# SecondSheet.net
KiCad netlist of a schematic drawn in Altium Designer
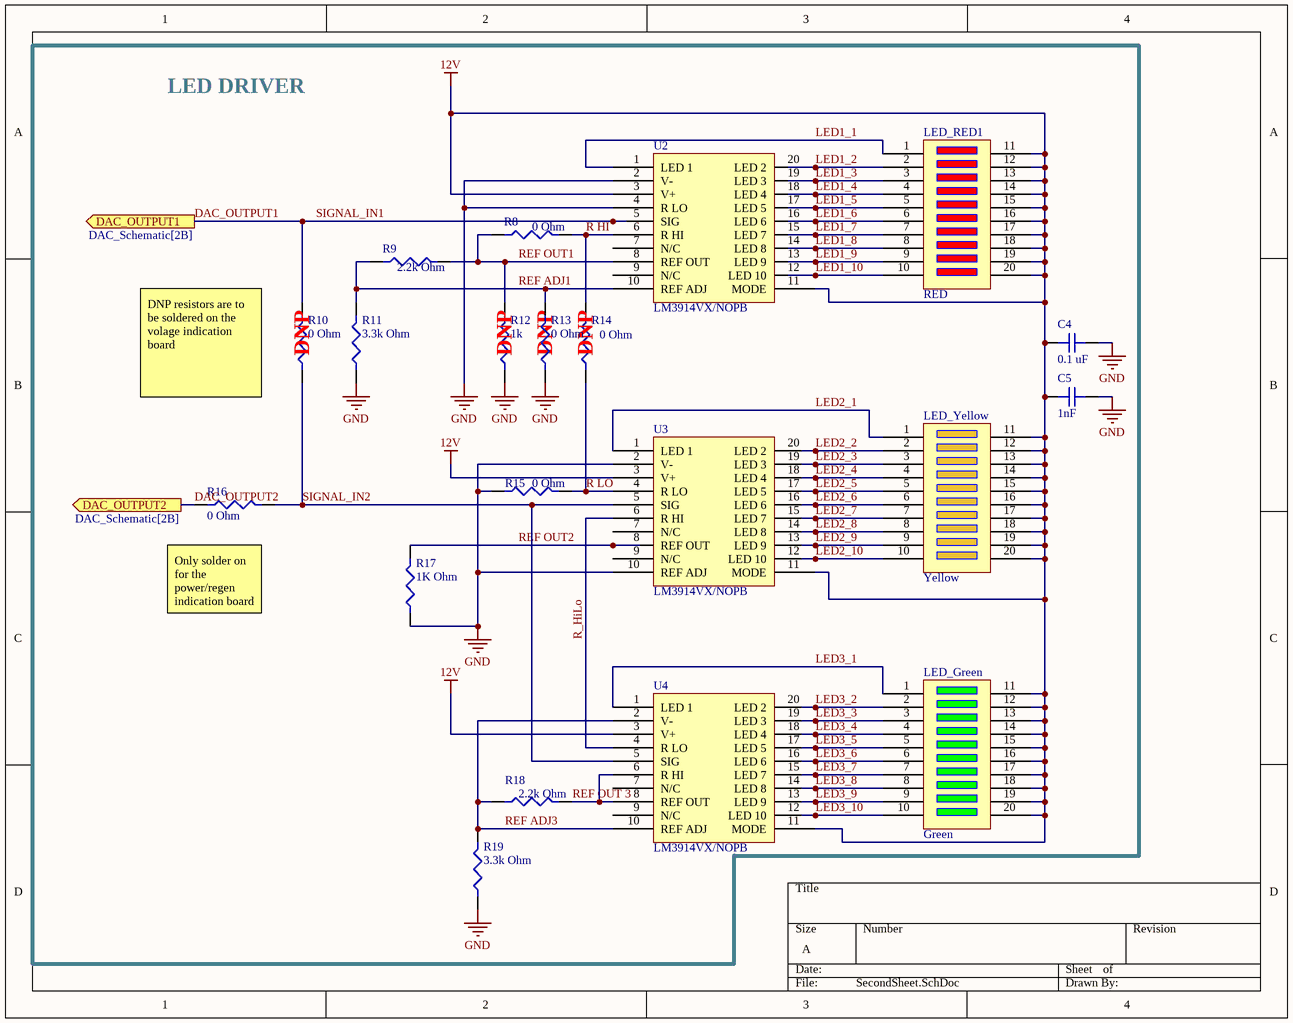
[diagram p0: SecondSheet.SchDoc]

(export (version "E")
  (design (tool "Eeschema 10.0.6"))
  (components
    (comp (ref "C4")
      (value "0.1 uF")
      (footprint "CAPC1608X09N")
      (fields
        (field (name "MANUFACTURER") "KEMET")
        (field (name "MANUFACTURER PART NUMBER") "C0603C104Z3VACTU")
        (field (name "TOLERANCE") "80%")
      )
      (libsource (lib "Dash_Schematic") (part "C0603C104Z3VACTU"))
    )
    (comp (ref "C5")
      (value "1nF")
      (footprint "CAPC1608X09N")
      (description "CAP CER 1000PF 50V X7R 0603")
      (fields
        (field (name "MANUFACTURER") "Yageo")
        (field (name "MANUFACTURER PART NUMBER") "CC0603KRX7R9BB102")
      )
      (libsource (lib "Dash_Schematic") (part "CC0603KRX7R9BB102"))
    )
    (comp (ref "LED_Green")
      (value "Green")
      (footprint "DIP20")
      (description "LED BAR GRAPH 10-SEGMENT GREEN")
      (fields
        (field (name "MANUFACTURER") "Vishay Lite-On")
        (field (name "MANUFACTURER PART NUMBER") "LTA-1000G")
      )
      (libsource (lib "Dash_Schematic") (part "LTA-1000G"))
    )
    (comp (ref "LED_RED1")
      (value "RED")
      (footprint "DIP20")
      (description "LED BAR GRAPH 10-SEGMENT RED")
      (fields
        (field (name "MANUFACTURER") "Vishay Lite-On")
        (field (name "MANUFACTURER PART NUMBER") "LTA-1000HR")
      )
      (libsource (lib "Dash_Schematic") (part "LTA-1000HR"))
    )
    (comp (ref "LED_Yellow")
      (value "Yellow")
      (footprint "DIP20")
      (description "LED BAR GRAPH 10-SEGMENT YELLOW")
      (fields
        (field (name "MANUFACTURER") "Vishay Lite-On")
        (field (name "MANUFACTURER PART NUMBER") "LTA-1000Y")
      )
      (libsource (lib "Dash_Schematic") (part "LTA-1000Y"))
    )
    (comp (ref "R8")
      (value "0 Ohm")
      (footprint "RESC2012X06N")
      (description "RES 0 OHM JUMPER 1/8W 0805")
      (fields
        (field (name "MANUFACTURER") "Stackpole Electronics")
        (field (name "MANUFACTURER PART NUMBER") "RMCF0805ZT0R00")
      )
      (libsource (lib "Dash_Schematic") (part "RMCF0805ZT0R00"))
    )
    (comp (ref "R9")
      (value "2.2k Ohm")
      (footprint "RESC2012X06N")
      (description "RES SMD 2.2K OHM 1% 1/8W 0805")
      (fields
        (field (name "MANUFACTURER") "Yageo")
        (field (name "MANUFACTURER PART NUMBER") "RC0805FR-072K2L")
      )
      (libsource (lib "Dash_Schematic") (part "RC0805FR-072K2L"))
    )
    (comp (ref "R10")
      (value "0 Ohm")
      (footprint "RESC2012X06N")
      (description "RES 0 OHM JUMPER 1/8W 0805")
      (fields
        (field (name "MANUFACTURER") "Stackpole Electronics")
        (field (name "MANUFACTURER PART NUMBER") "RMCF0805ZT0R00")
      )
      (libsource (lib "Dash_Schematic") (part "RMCF0805ZT0R00"))
    )
    (comp (ref "R11")
      (value "3.3k Ohm")
      (footprint "RESC2012X06N")
      (description "Thin Film Resistors - SMD 0805 1/8W 3.3Kohms")
      (fields
        (field (name "MANUFACTURER") "Panasonic")
        (field (name "MANUFACTURER PART NUMBER") "ERA-6AEB332V")
      )
      (libsource (lib "Dash_Schematic") (part "ERA-6AEB332V"))
    )
    (comp (ref "R12")
      (value "1k")
      (footprint "RESC2012X06N")
      (description "RES 0 OHM JUMPER 1/8W 0805")
      (fields
        (field (name "MANUFACTURER") "Stackpole Electronics")
        (field (name "MANUFACTURER PART NUMBER") "RMCF0805ZT0R00")
      )
      (libsource (lib "Dash_Schematic") (part "RMCF0805ZT0R00"))
    )
    (comp (ref "R13")
      (value "0 Ohm")
      (footprint "RESC2012X06N")
      (description "RES 0 OHM JUMPER 1/8W 0805")
      (fields
        (field (name "MANUFACTURER") "Stackpole Electronics")
        (field (name "MANUFACTURER PART NUMBER") "RMCF0805ZT0R00")
      )
      (libsource (lib "Dash_Schematic") (part "RMCF0805ZT0R00"))
    )
    (comp (ref "R14")
      (value "0 Ohm")
      (footprint "RESC2012X06N")
      (description "RES 0 OHM JUMPER 1/8W 0805")
      (fields
        (field (name "MANUFACTURER") "Stackpole Electronics")
        (field (name "MANUFACTURER PART NUMBER") "RMCF0805ZT0R00")
      )
      (libsource (lib "Dash_Schematic") (part "RMCF0805ZT0R00"))
    )
    (comp (ref "R15")
      (value "0 Ohm")
      (footprint "RESC2012X06N")
      (description "RES 0 OHM JUMPER 1/8W 0805")
      (fields
        (field (name "MANUFACTURER") "Stackpole Electronics")
        (field (name "MANUFACTURER PART NUMBER") "RMCF0805ZT0R00")
      )
      (libsource (lib "Dash_Schematic") (part "RMCF0805ZT0R00"))
    )
    (comp (ref "R16")
      (value "0 Ohm")
      (footprint "RESC2012X06N")
      (description "RES 0 OHM JUMPER 1/8W 0805")
      (fields
        (field (name "MANUFACTURER") "Stackpole Electronics")
        (field (name "MANUFACTURER PART NUMBER") "RMCF0805ZT0R00")
      )
      (libsource (lib "Dash_Schematic") (part "RMCF0805ZT0R00"))
    )
    (comp (ref "R17")
      (value "1K Ohm")
      (footprint "RESC2012X06N")
      (description "RES SMD 1K OHM 5% 1/8W 0805")
      (fields
        (field (name "MANUFACTURER") "Yageo")
        (field (name "MANUFACTURER PART NUMBER") "RC0805JR-071KL")
      )
      (libsource (lib "Dash_Schematic") (part "RC0805JR-071KL"))
    )
    (comp (ref "R18")
      (value "2.2k Ohm")
      (footprint "RESC2012X06N")
      (description "RES SMD 2.2K OHM 1% 1/8W 0805")
      (fields
        (field (name "MANUFACTURER") "Yageo")
        (field (name "MANUFACTURER PART NUMBER") "RC0805FR-072K2L")
      )
      (libsource (lib "Dash_Schematic") (part "RC0805FR-072K2L"))
    )
    (comp (ref "R19")
      (value "3.3k Ohm")
      (footprint "RESC2012X06N")
      (description "Thin Film Resistors - SMD 0805 1/8W 3.3Kohms")
      (fields
        (field (name "MANUFACTURER") "Panasonic")
        (field (name "MANUFACTURER PART NUMBER") "ERA-6AEB332V")
      )
      (libsource (lib "Dash_Schematic") (part "ERA-6AEB332V"))
    )
    (comp (ref "U2")
      (value "LM3914VX/NOPB")
      (footprint "PLCC127P990X990X457-20N")
      (description "LED DRVR 10Segment 20-Pin PLCC T/R")
      (fields (field (name "MANUFACTURER") "TI National Semiconductor"))
      (libsource (lib "Dash_Schematic") (part "LM3914VX/NOPB"))
    )
    (comp (ref "U3")
      (value "LM3914VX/NOPB")
      (footprint "PLCC127P990X990X457-20N")
      (description "LED DRVR 10Segment 20-Pin PLCC T/R")
      (fields (field (name "MANUFACTURER") "TI National Semiconductor"))
      (libsource (lib "Dash_Schematic") (part "LM3914VX/NOPB"))
    )
    (comp (ref "U4")
      (value "LM3914VX/NOPB")
      (footprint "PLCC127P990X990X457-20N")
      (description "LED DRVR 10Segment 20-Pin PLCC T/R")
      (fields (field (name "MANUFACTURER") "TI National Semiconductor"))
      (libsource (lib "Dash_Schematic") (part "LM3914VX/NOPB"))
    )
  )
  (nets
    (net (code "1") (name "/DAC_OUTPUT1") (class "Default")
      (node (ref "R10") (pin "2") (pinfunction "2_2") (pintype "passive"))
      (node (ref "U2") (pin "5") (pinfunction "SIG_5") (pintype "passive"))
    )
    (net (code "2") (name "/DAC_OUTPUT2") (class "Default")
      (node (ref "R16") (pin "1") (pinfunction "1_1") (pintype "passive"))
    )
    (net (code "3") (name "/LED1_1") (class "Default")
      (node (ref "LED_RED1") (pin "1") (pinfunction "1_1") (pintype "passive"))
      (node (ref "U2") (pin "1") (pinfunction "LED_1_1") (pintype "passive"))
    )
    (net (code "4") (name "/LED1_2") (class "Default")
      (node (ref "LED_RED1") (pin "2") (pinfunction "2_2") (pintype "passive"))
      (node (ref "U2") (pin "20") (pinfunction "LED_2_20") (pintype "passive"))
    )
    (net (code "5") (name "/LED1_3") (class "Default")
      (node (ref "LED_RED1") (pin "3") (pinfunction "3_3") (pintype "passive"))
      (node (ref "U2") (pin "19") (pinfunction "LED_3_19") (pintype "passive"))
    )
    (net (code "6") (name "/LED1_4") (class "Default")
      (node (ref "LED_RED1") (pin "4") (pinfunction "4_4") (pintype "passive"))
      (node (ref "U2") (pin "18") (pinfunction "LED_4_18") (pintype "passive"))
    )
    (net (code "7") (name "/LED1_5") (class "Default")
      (node (ref "LED_RED1") (pin "5") (pinfunction "5_5") (pintype "passive"))
      (node (ref "U2") (pin "17") (pinfunction "LED_5_17") (pintype "passive"))
    )
    (net (code "8") (name "/LED1_6") (class "Default")
      (node (ref "LED_RED1") (pin "6") (pinfunction "6_6") (pintype "passive"))
      (node (ref "U2") (pin "16") (pinfunction "LED_6_16") (pintype "passive"))
    )
    (net (code "9") (name "/LED1_7") (class "Default")
      (node (ref "LED_RED1") (pin "7") (pinfunction "7_7") (pintype "passive"))
      (node (ref "U2") (pin "15") (pinfunction "LED_7_15") (pintype "passive"))
    )
    (net (code "10") (name "/LED1_8") (class "Default")
      (node (ref "LED_RED1") (pin "8") (pinfunction "8_8") (pintype "passive"))
      (node (ref "U2") (pin "14") (pinfunction "LED_8_14") (pintype "passive"))
    )
    (net (code "11") (name "/LED1_9") (class "Default")
      (node (ref "LED_RED1") (pin "9") (pinfunction "9_9") (pintype "passive"))
      (node (ref "U2") (pin "13") (pinfunction "LED_9_13") (pintype "passive"))
    )
    (net (code "12") (name "/LED1_10") (class "Default")
      (node (ref "LED_RED1") (pin "10") (pinfunction "10_10") (pintype "passive"))
      (node (ref "U2") (pin "12") (pinfunction "LED_10_12") (pintype "passive"))
    )
    (net (code "13") (name "/LED2_1") (class "Default")
      (node (ref "LED_Yellow") (pin "1") (pinfunction "1_1") (pintype "passive"))
      (node (ref "U3") (pin "1") (pinfunction "LED_1_1") (pintype "passive"))
    )
    (net (code "14") (name "/LED2_2") (class "Default")
      (node (ref "LED_Yellow") (pin "2") (pinfunction "2_2") (pintype "passive"))
      (node (ref "U3") (pin "20") (pinfunction "LED_2_20") (pintype "passive"))
    )
    (net (code "15") (name "/LED2_3") (class "Default")
      (node (ref "LED_Yellow") (pin "3") (pinfunction "3_3") (pintype "passive"))
      (node (ref "U3") (pin "19") (pinfunction "LED_3_19") (pintype "passive"))
    )
    (net (code "16") (name "/LED2_4") (class "Default")
      (node (ref "LED_Yellow") (pin "4") (pinfunction "4_4") (pintype "passive"))
      (node (ref "U3") (pin "18") (pinfunction "LED_4_18") (pintype "passive"))
    )
    (net (code "17") (name "/LED2_5") (class "Default")
      (node (ref "LED_Yellow") (pin "5") (pinfunction "5_5") (pintype "passive"))
      (node (ref "U3") (pin "17") (pinfunction "LED_5_17") (pintype "passive"))
    )
    (net (code "18") (name "/LED2_6") (class "Default")
      (node (ref "LED_Yellow") (pin "6") (pinfunction "6_6") (pintype "passive"))
      (node (ref "U3") (pin "16") (pinfunction "LED_6_16") (pintype "passive"))
    )
    (net (code "19") (name "/LED2_7") (class "Default")
      (node (ref "LED_Yellow") (pin "7") (pinfunction "7_7") (pintype "passive"))
      (node (ref "U3") (pin "15") (pinfunction "LED_7_15") (pintype "passive"))
    )
    (net (code "20") (name "/LED2_8") (class "Default")
      (node (ref "LED_Yellow") (pin "8") (pinfunction "8_8") (pintype "passive"))
      (node (ref "U3") (pin "14") (pinfunction "LED_8_14") (pintype "passive"))
    )
    (net (code "21") (name "/LED2_9") (class "Default")
      (node (ref "LED_Yellow") (pin "9") (pinfunction "9_9") (pintype "passive"))
      (node (ref "U3") (pin "13") (pinfunction "LED_9_13") (pintype "passive"))
    )
    (net (code "22") (name "/LED2_10") (class "Default")
      (node (ref "LED_Yellow") (pin "10") (pinfunction "10_10") (pintype "passive"))
      (node (ref "U3") (pin "12") (pinfunction "LED_10_12") (pintype "passive"))
    )
    (net (code "23") (name "/LED3_1") (class "Default")
      (node (ref "LED_Green") (pin "1") (pinfunction "1_1") (pintype "passive"))
      (node (ref "U4") (pin "1") (pinfunction "LED_1_1") (pintype "passive"))
    )
    (net (code "24") (name "/LED3_2") (class "Default")
      (node (ref "LED_Green") (pin "2") (pinfunction "2_2") (pintype "passive"))
      (node (ref "U4") (pin "20") (pinfunction "LED_2_20") (pintype "passive"))
    )
    (net (code "25") (name "/LED3_3") (class "Default")
      (node (ref "LED_Green") (pin "3") (pinfunction "3_3") (pintype "passive"))
      (node (ref "U4") (pin "19") (pinfunction "LED_3_19") (pintype "passive"))
    )
    (net (code "26") (name "/LED3_4") (class "Default")
      (node (ref "LED_Green") (pin "4") (pinfunction "4_4") (pintype "passive"))
      (node (ref "U4") (pin "18") (pinfunction "LED_4_18") (pintype "passive"))
    )
    (net (code "27") (name "/LED3_5") (class "Default")
      (node (ref "LED_Green") (pin "5") (pinfunction "5_5") (pintype "passive"))
      (node (ref "U4") (pin "17") (pinfunction "LED_5_17") (pintype "passive"))
    )
    (net (code "28") (name "/LED3_6") (class "Default")
      (node (ref "LED_Green") (pin "6") (pinfunction "6_6") (pintype "passive"))
      (node (ref "U4") (pin "16") (pinfunction "LED_6_16") (pintype "passive"))
    )
    (net (code "29") (name "/LED3_7") (class "Default")
      (node (ref "LED_Green") (pin "7") (pinfunction "7_7") (pintype "passive"))
      (node (ref "U4") (pin "15") (pinfunction "LED_7_15") (pintype "passive"))
    )
    (net (code "30") (name "/LED3_8") (class "Default")
      (node (ref "LED_Green") (pin "8") (pinfunction "8_8") (pintype "passive"))
      (node (ref "U4") (pin "14") (pinfunction "LED_8_14") (pintype "passive"))
    )
    (net (code "31") (name "/LED3_9") (class "Default")
      (node (ref "LED_Green") (pin "9") (pinfunction "9_9") (pintype "passive"))
      (node (ref "U4") (pin "13") (pinfunction "LED_9_13") (pintype "passive"))
    )
    (net (code "32") (name "/LED3_10") (class "Default")
      (node (ref "LED_Green") (pin "10") (pinfunction "10_10") (pintype "passive"))
      (node (ref "U4") (pin "12") (pinfunction "LED_10_12") (pintype "passive"))
    )
    (net (code "33") (name "/R HI") (class "Default")
      (node (ref "R14") (pin "2") (pinfunction "2_2") (pintype "passive"))
      (node (ref "R8") (pin "2") (pinfunction "2_2") (pintype "passive"))
      (node (ref "U2") (pin "6") (pinfunction "R_HI_6") (pintype "passive"))
    )
    (net (code "34") (name "/R LO") (class "Default")
      (node (ref "R14") (pin "1") (pinfunction "1_1") (pintype "passive"))
      (node (ref "R15") (pin "2") (pinfunction "2_2") (pintype "passive"))
      (node (ref "U3") (pin "4") (pinfunction "R_LO_4") (pintype "passive"))
    )
    (net (code "35") (name "/REF ADJ1") (class "Default")
      (node (ref "R11") (pin "2") (pinfunction "2_2") (pintype "passive"))
      (node (ref "R13") (pin "2") (pinfunction "2_2") (pintype "passive"))
      (node (ref "R9") (pin "1") (pinfunction "1_1") (pintype "passive"))
      (node (ref "U2") (pin "10") (pinfunction "REF_ADJ_10") (pintype "passive"))
    )
    (net (code "36") (name "/REF ADJ3") (class "Default")
      (node (ref "R18") (pin "1") (pinfunction "1_1") (pintype "passive"))
      (node (ref "R19") (pin "2") (pinfunction "2_2") (pintype "passive"))
      (node (ref "U4") (pin "10") (pinfunction "REF_ADJ_10") (pintype "passive"))
      (node (ref "U4") (pin "2") (pinfunction "V-_2") (pintype "passive"))
    )
    (net (code "37") (name "/REF OUT 3") (class "Default")
      (node (ref "R18") (pin "2") (pinfunction "2_2") (pintype "passive"))
      (node (ref "U4") (pin "6") (pinfunction "R_HI_6") (pintype "passive"))
      (node (ref "U4") (pin "8") (pinfunction "REF_OUT_8") (pintype "passive"))
    )
    (net (code "38") (name "/REF OUT1") (class "Default")
      (node (ref "R12") (pin "2") (pinfunction "2_2") (pintype "passive"))
      (node (ref "R8") (pin "1") (pinfunction "1_1") (pintype "passive"))
      (node (ref "R9") (pin "2") (pinfunction "2_2") (pintype "passive"))
      (node (ref "U2") (pin "8") (pinfunction "REF_OUT_8") (pintype "passive"))
    )
    (net (code "39") (name "/REF OUT2") (class "Default")
      (node (ref "R17") (pin "2") (pinfunction "2_2") (pintype "passive"))
      (node (ref "U3") (pin "8") (pinfunction "REF_OUT_8") (pintype "passive"))
    )
    (net (code "40") (name "/R_HiLo") (class "Default")
      (node (ref "U3") (pin "6") (pinfunction "R_HI_6") (pintype "passive"))
      (node (ref "U4") (pin "4") (pinfunction "R_LO_4") (pintype "passive"))
    )
    (net (code "41") (name "/SIGNAL_IN2") (class "Default")
      (node (ref "R10") (pin "1") (pinfunction "1_1") (pintype "passive"))
      (node (ref "R16") (pin "2") (pinfunction "2_2") (pintype "passive"))
      (node (ref "U3") (pin "5") (pinfunction "SIG_5") (pintype "passive"))
      (node (ref "U4") (pin "5") (pinfunction "SIG_5") (pintype "passive"))
    )
    (net (code "42") (name "12V") (class "Default")
      (node (ref "C4") (pin "1") (pinfunction "1_1") (pintype "passive"))
      (node (ref "C5") (pin "1") (pinfunction "1_1") (pintype "passive"))
      (node (ref "LED_Green") (pin "11") (pinfunction "11_11") (pintype "passive"))
      (node (ref "LED_Green") (pin "12") (pinfunction "12_12") (pintype "passive"))
      (node (ref "LED_Green") (pin "13") (pinfunction "13_13") (pintype "passive"))
      (node (ref "LED_Green") (pin "14") (pinfunction "14_14") (pintype "passive"))
      (node (ref "LED_Green") (pin "15") (pinfunction "15_15") (pintype "passive"))
      (node (ref "LED_Green") (pin "16") (pinfunction "16_16") (pintype "passive"))
      (node (ref "LED_Green") (pin "17") (pinfunction "17_17") (pintype "passive"))
      (node (ref "LED_Green") (pin "18") (pinfunction "18_18") (pintype "passive"))
      (node (ref "LED_Green") (pin "19") (pinfunction "19_19") (pintype "passive"))
      (node (ref "LED_Green") (pin "20") (pinfunction "20_20") (pintype "passive"))
      (node (ref "LED_RED1") (pin "11") (pinfunction "11_11") (pintype "passive"))
      (node (ref "LED_RED1") (pin "12") (pinfunction "12_12") (pintype "passive"))
      (node (ref "LED_RED1") (pin "13") (pinfunction "13_13") (pintype "passive"))
      (node (ref "LED_RED1") (pin "14") (pinfunction "14_14") (pintype "passive"))
      (node (ref "LED_RED1") (pin "15") (pinfunction "15_15") (pintype "passive"))
      (node (ref "LED_RED1") (pin "16") (pinfunction "16_16") (pintype "passive"))
      (node (ref "LED_RED1") (pin "17") (pinfunction "17_17") (pintype "passive"))
      (node (ref "LED_RED1") (pin "18") (pinfunction "18_18") (pintype "passive"))
      (node (ref "LED_RED1") (pin "19") (pinfunction "19_19") (pintype "passive"))
      (node (ref "LED_RED1") (pin "20") (pinfunction "20_20") (pintype "passive"))
      (node (ref "LED_Yellow") (pin "11") (pinfunction "11_11") (pintype "passive"))
      (node (ref "LED_Yellow") (pin "12") (pinfunction "12_12") (pintype "passive"))
      (node (ref "LED_Yellow") (pin "13") (pinfunction "13_13") (pintype "passive"))
      (node (ref "LED_Yellow") (pin "14") (pinfunction "14_14") (pintype "passive"))
      (node (ref "LED_Yellow") (pin "15") (pinfunction "15_15") (pintype "passive"))
      (node (ref "LED_Yellow") (pin "16") (pinfunction "16_16") (pintype "passive"))
      (node (ref "LED_Yellow") (pin "17") (pinfunction "17_17") (pintype "passive"))
      (node (ref "LED_Yellow") (pin "18") (pinfunction "18_18") (pintype "passive"))
      (node (ref "LED_Yellow") (pin "19") (pinfunction "19_19") (pintype "passive"))
      (node (ref "LED_Yellow") (pin "20") (pinfunction "20_20") (pintype "passive"))
      (node (ref "U2") (pin "11") (pinfunction "MODE_11") (pintype "passive"))
      (node (ref "U2") (pin "3") (pinfunction "V+_3") (pintype "passive"))
      (node (ref "U3") (pin "11") (pinfunction "MODE_11") (pintype "passive"))
      (node (ref "U3") (pin "3") (pinfunction "V+_3") (pintype "passive"))
      (node (ref "U4") (pin "11") (pinfunction "MODE_11") (pintype "passive"))
      (node (ref "U4") (pin "3") (pinfunction "V+_3") (pintype "passive"))
    )
    (net (code "43") (name "GND") (class "Default")
      (node (ref "C4") (pin "2") (pinfunction "2_2") (pintype "passive"))
      (node (ref "C5") (pin "2") (pinfunction "2_2") (pintype "passive"))
      (node (ref "R11") (pin "1") (pinfunction "1_1") (pintype "passive"))
      (node (ref "R12") (pin "1") (pinfunction "1_1") (pintype "passive"))
      (node (ref "R13") (pin "1") (pinfunction "1_1") (pintype "passive"))
      (node (ref "R15") (pin "1") (pinfunction "1_1") (pintype "passive"))
      (node (ref "R17") (pin "1") (pinfunction "1_1") (pintype "passive"))
      (node (ref "R19") (pin "1") (pinfunction "1_1") (pintype "passive"))
      (node (ref "U2") (pin "2") (pinfunction "V-_2") (pintype "passive"))
      (node (ref "U2") (pin "4") (pinfunction "R_LO_4") (pintype "passive"))
      (node (ref "U3") (pin "10") (pinfunction "REF_ADJ_10") (pintype "passive"))
      (node (ref "U3") (pin "2") (pinfunction "V-_2") (pintype "passive"))
    )
    (net (code "44") (name "unconnected-(U2-N{slash}C-Pad7)") (class "Default")
      (node (ref "U2") (pin "7") (pinfunction "N/C_7") (pintype "passive"))
    )
    (net (code "45") (name "unconnected-(U2-N{slash}C-Pad9)") (class "Default")
      (node (ref "U2") (pin "9") (pinfunction "N/C_9") (pintype "passive"))
    )
    (net (code "46") (name "unconnected-(U3-N{slash}C-Pad7)") (class "Default")
      (node (ref "U3") (pin "7") (pinfunction "N/C_7") (pintype "passive"))
    )
    (net (code "47") (name "unconnected-(U3-N{slash}C-Pad9)") (class "Default")
      (node (ref "U3") (pin "9") (pinfunction "N/C_9") (pintype "passive"))
    )
    (net (code "48") (name "unconnected-(U4-N{slash}C-Pad7)") (class "Default")
      (node (ref "U4") (pin "7") (pinfunction "N/C_7") (pintype "passive"))
    )
    (net (code "49") (name "unconnected-(U4-N{slash}C-Pad9)") (class "Default")
      (node (ref "U4") (pin "9") (pinfunction "N/C_9") (pintype "passive"))
    )
  )
)
